# TSE_mother_board_CPU_commutation.net
KiCad netlist of a schematic drawn in Altium Designer
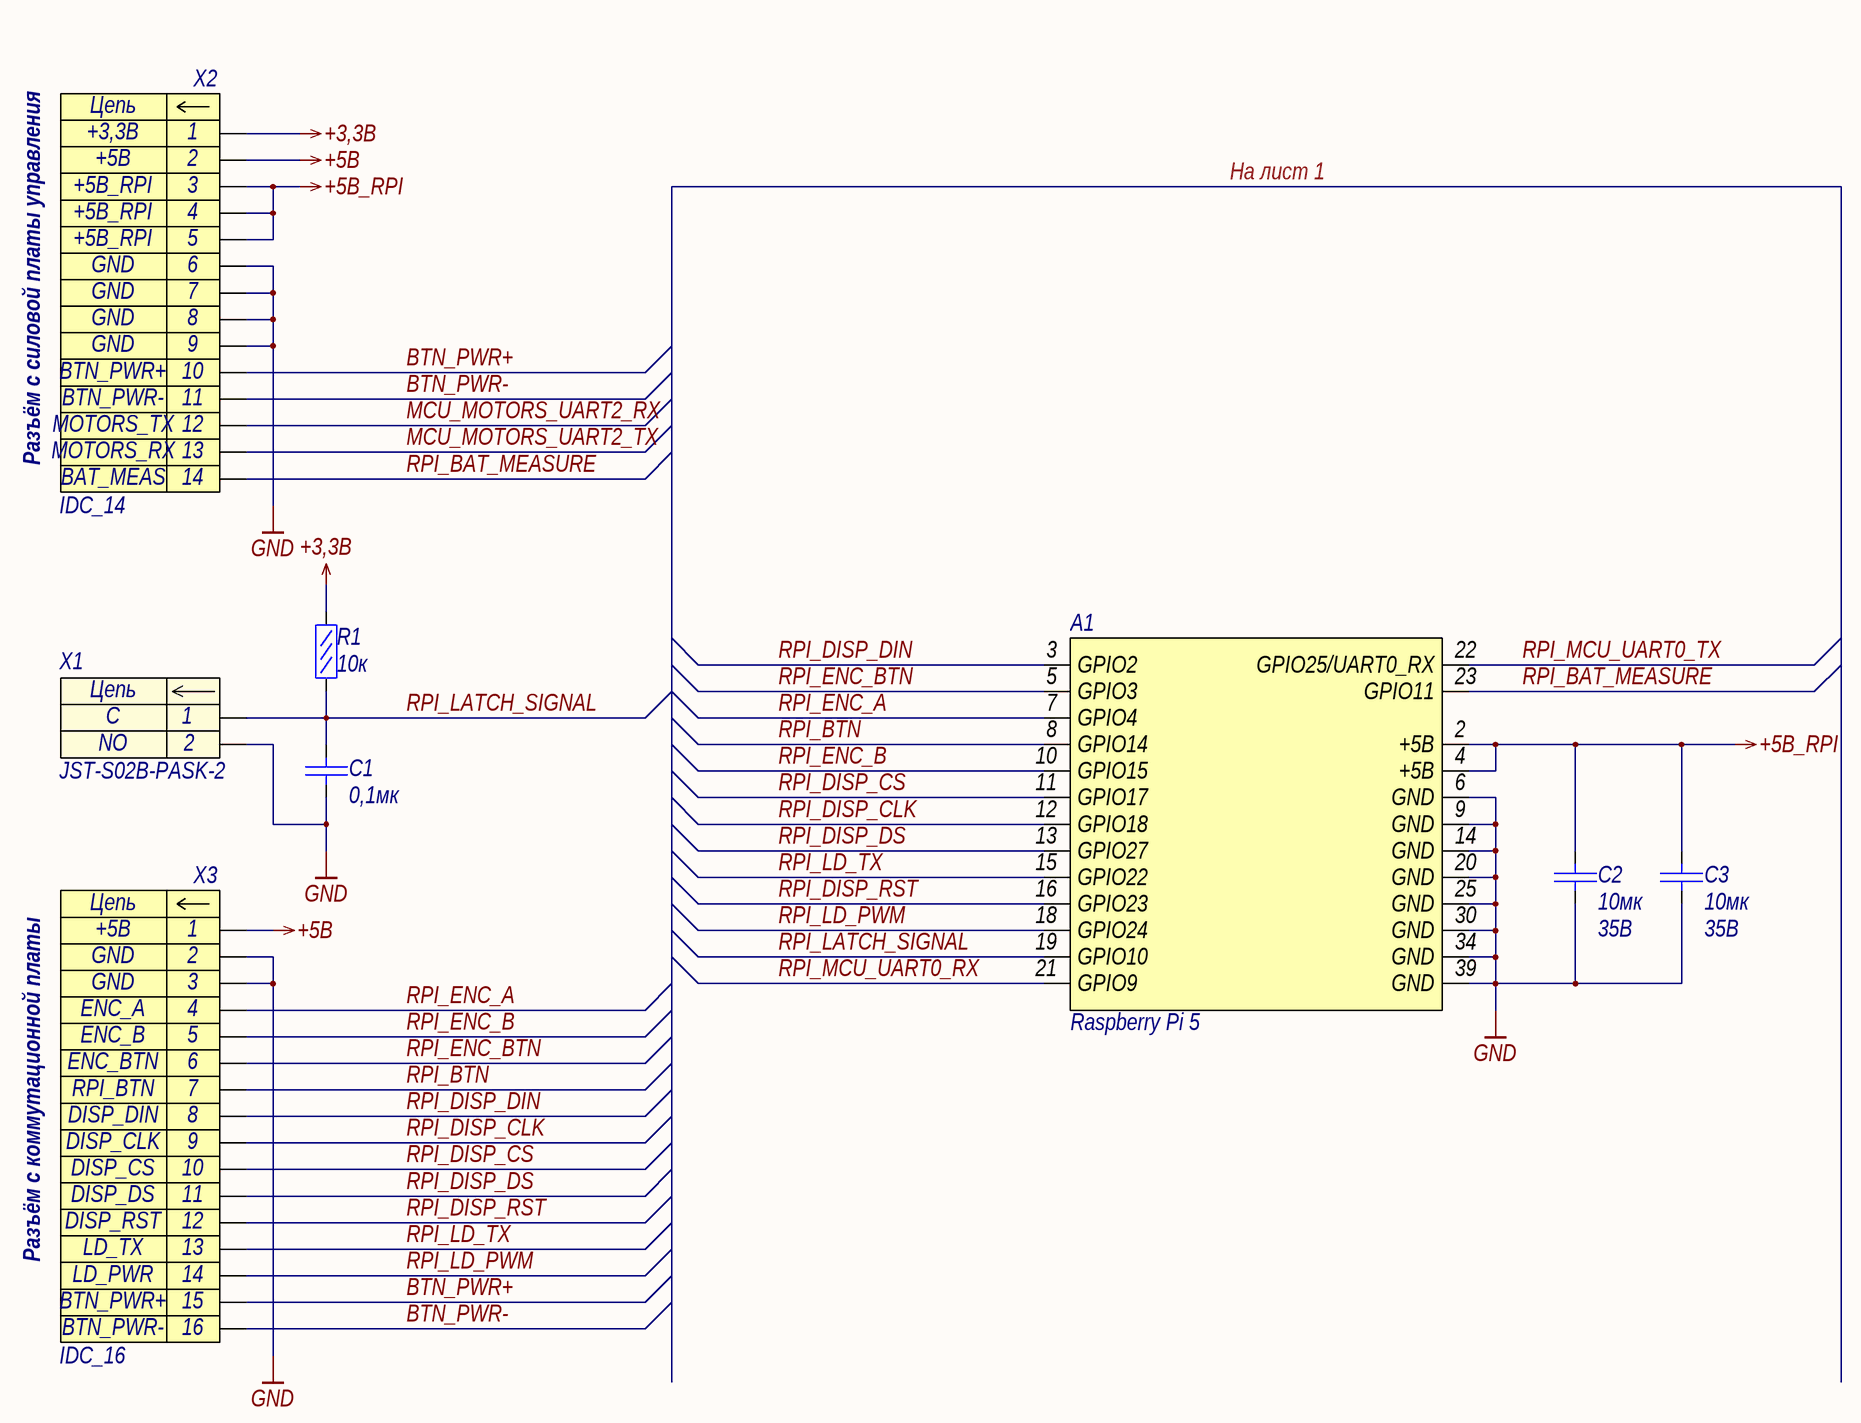
[diagram p0: TSE_mother_board_CPU_commutation.SchDoc]

(export (version "E")
  (design (tool "Eeschema 10.0.6"))
  (components
    (comp (ref "A1")
      (value "Raspberry Pi 5")
      (footprint "PLS_40")
      (description "Микрокомпьютер")
      (libsource (lib "ics") (part "Raspberry Pi 5"))
    )
    (comp (ref "C1")
      (value "0,1мк")
      (footprint "C0603")
      (description "Конденсатор кер. 0,1мкФ 50В")
      (fields (field (name "MANUFACTURER") "Yageo"))
      (libsource (lib "capacitors") (part "CC0603JPX7R9BB104"))
    )
    (comp (ref "C2")
      (value "10мк")
      (footprint "C1210")
      (description "Конденсатор кер. 10мкФ 35В")
      (fields (field (name "MANUFACTURER") "Yageo") (field (name "VOLTAGE") "35В"))
      (libsource (lib "capacitors") (part "CL32A106KATLNNE"))
    )
    (comp (ref "C3")
      (value "10мк")
      (footprint "C1210")
      (description "Конденсатор кер. 10мкФ 35В")
      (fields (field (name "MANUFACTURER") "Yageo") (field (name "VOLTAGE") "35В"))
      (libsource (lib "capacitors") (part "CL32A106KATLNNE"))
    )
    (comp (ref "R1")
      (value "10к")
      (footprint "R0603")
      (description "Резистор 10кОм 0,063Вт 1%")
      (fields (field (name "MANUFACTURER") "YAGEO") (field (name "TOLERANCE") "1%"))
      (libsource (lib "resistors") (part "RC0603FR-0710KL"))
    )
    (comp (ref "X1")
      (value "JST-S02B-PASK-2")
      (footprint "JST-S02B-PASK-2")
      (description "Разъем - 2 конт. угловая вилка на плату, шаг 2,00 мм")
      (libsource (lib "headers") (part "JST-S02B-PASK-2"))
    )
    (comp (ref "X2")
      (value "IDC_14")
      (footprint "IDC1.27_14")
      (description "Разъем - 14 конт. прямая вилка на плату")
      (libsource (lib "headers") (part "IDC_14"))
    )
    (comp (ref "X3")
      (value "IDC_16")
      (footprint "IDC1.27_16")
      (description "Разъем - 16 конт. прямая вилка на плату")
      (libsource (lib "headers") (part "IDC_16"))
    )
  )
  (nets
    (net (code "1") (name "+3,3В") (class "Default")
      (node (ref "R1") (pin "2") (pinfunction "2_2") (pintype "passive"))
      (node (ref "X2") (pin "1") (pinfunction "1_1") (pintype "passive"))
    )
    (net (code "2") (name "+5В") (class "Default")
      (node (ref "X2") (pin "2") (pinfunction "2_2") (pintype "passive"))
      (node (ref "X3") (pin "1") (pinfunction "1_1") (pintype "passive"))
    )
    (net (code "3") (name "+5В_RPI") (class "Default")
      (node (ref "A1") (pin "2") (pinfunction "+5В_2") (pintype "passive"))
      (node (ref "A1") (pin "4") (pinfunction "+5В_4") (pintype "passive"))
      (node (ref "C2") (pin "2") (pinfunction "2_2") (pintype "passive"))
      (node (ref "C3") (pin "2") (pinfunction "2_2") (pintype "passive"))
      (node (ref "X2") (pin "3") (pinfunction "3_3") (pintype "passive"))
      (node (ref "X2") (pin "4") (pinfunction "4_4") (pintype "passive"))
      (node (ref "X2") (pin "5") (pinfunction "5_5") (pintype "passive"))
    )
    (net (code "4") (name "/BTN_PWR+") (class "Default")
      (node (ref "X2") (pin "10") (pinfunction "10_10") (pintype "passive"))
      (node (ref "X3") (pin "15") (pinfunction "15_15") (pintype "passive"))
    )
    (net (code "5") (name "/BTN_PWR-") (class "Default")
      (node (ref "X2") (pin "11") (pinfunction "11_11") (pintype "passive"))
      (node (ref "X3") (pin "16") (pinfunction "16_16") (pintype "passive"))
    )
    (net (code "6") (name "/MCU_MOTORS_UART2_RX") (class "Default")
      (node (ref "X2") (pin "12") (pinfunction "12_12") (pintype "passive"))
    )
    (net (code "7") (name "/MCU_MOTORS_UART2_TX") (class "Default")
      (node (ref "X2") (pin "13") (pinfunction "13_13") (pintype "passive"))
    )
    (net (code "8") (name "/RPI_BAT_MEASURE") (class "Default")
      (node (ref "A1") (pin "23") (pinfunction "GPIO11_23") (pintype "passive"))
      (node (ref "X2") (pin "14") (pinfunction "14_14") (pintype "passive"))
    )
    (net (code "9") (name "/RPI_BTN") (class "Default")
      (node (ref "A1") (pin "8") (pinfunction "GPIO14_8") (pintype "passive"))
      (node (ref "X3") (pin "7") (pinfunction "7_7") (pintype "passive"))
    )
    (net (code "10") (name "/RPI_DISP_CLK") (class "Default")
      (node (ref "A1") (pin "12") (pinfunction "GPIO18_12") (pintype "passive"))
      (node (ref "X3") (pin "9") (pinfunction "9_9") (pintype "passive"))
    )
    (net (code "11") (name "/RPI_DISP_CS") (class "Default")
      (node (ref "A1") (pin "11") (pinfunction "GPIO17_11") (pintype "passive"))
      (node (ref "X3") (pin "10") (pinfunction "10_10") (pintype "passive"))
    )
    (net (code "12") (name "/RPI_DISP_DIN") (class "Default")
      (node (ref "A1") (pin "3") (pinfunction "GPIO2_3") (pintype "passive"))
      (node (ref "X3") (pin "8") (pinfunction "8_8") (pintype "passive"))
    )
    (net (code "13") (name "/RPI_DISP_DS") (class "Default")
      (node (ref "A1") (pin "13") (pinfunction "GPIO27_13") (pintype "passive"))
      (node (ref "X3") (pin "11") (pinfunction "11_11") (pintype "passive"))
    )
    (net (code "14") (name "/RPI_DISP_RST") (class "Default")
      (node (ref "A1") (pin "16") (pinfunction "GPIO23_16") (pintype "passive"))
      (node (ref "X3") (pin "12") (pinfunction "12_12") (pintype "passive"))
    )
    (net (code "15") (name "/RPI_ENC_A") (class "Default")
      (node (ref "A1") (pin "7") (pinfunction "GPIO4_7") (pintype "passive"))
      (node (ref "X3") (pin "4") (pinfunction "4_4") (pintype "passive"))
    )
    (net (code "16") (name "/RPI_ENC_B") (class "Default")
      (node (ref "A1") (pin "10") (pinfunction "GPIO15_10") (pintype "passive"))
      (node (ref "X3") (pin "5") (pinfunction "5_5") (pintype "passive"))
    )
    (net (code "17") (name "/RPI_ENC_BTN") (class "Default")
      (node (ref "A1") (pin "5") (pinfunction "GPIO3_5") (pintype "passive"))
      (node (ref "X3") (pin "6") (pinfunction "6_6") (pintype "passive"))
    )
    (net (code "18") (name "/RPI_LATCH_SIGNAL") (class "Default")
      (node (ref "A1") (pin "19") (pinfunction "GPIO10_19") (pintype "passive"))
      (node (ref "C1") (pin "2") (pinfunction "2_2") (pintype "passive"))
      (node (ref "R1") (pin "1") (pinfunction "1_1") (pintype "passive"))
      (node (ref "X1") (pin "1") (pinfunction "1_1") (pintype "passive"))
    )
    (net (code "19") (name "/RPI_LD_PWM") (class "Default")
      (node (ref "A1") (pin "18") (pinfunction "GPIO24_18") (pintype "passive"))
      (node (ref "X3") (pin "14") (pinfunction "14_14") (pintype "passive"))
    )
    (net (code "20") (name "/RPI_LD_TX") (class "Default")
      (node (ref "A1") (pin "15") (pinfunction "GPIO22_15") (pintype "passive"))
      (node (ref "X3") (pin "13") (pinfunction "13_13") (pintype "passive"))
    )
    (net (code "21") (name "/RPI_MCU_UART0_RX") (class "Default")
      (node (ref "A1") (pin "21") (pinfunction "GPIO9_21") (pintype "passive"))
    )
    (net (code "22") (name "/RPI_MCU_UART0_TX") (class "Default")
      (node (ref "A1") (pin "22") (pinfunction "GPIO25/UART0_RX_22") (pintype "passive"))
    )
    (net (code "23") (name "GND") (class "Default")
      (node (ref "A1") (pin "14") (pinfunction "GND_14") (pintype "passive"))
      (node (ref "A1") (pin "20") (pinfunction "GND_20") (pintype "passive"))
      (node (ref "A1") (pin "25") (pinfunction "GND_25") (pintype "passive"))
      (node (ref "A1") (pin "30") (pinfunction "GND_30") (pintype "passive"))
      (node (ref "A1") (pin "34") (pinfunction "GND_34") (pintype "passive"))
      (node (ref "A1") (pin "39") (pinfunction "GND_39") (pintype "passive"))
      (node (ref "A1") (pin "6") (pinfunction "GND_6") (pintype "passive"))
      (node (ref "A1") (pin "9") (pinfunction "GND_9") (pintype "passive"))
      (node (ref "C1") (pin "1") (pinfunction "1_1") (pintype "passive"))
      (node (ref "C2") (pin "1") (pinfunction "1_1") (pintype "passive"))
      (node (ref "C3") (pin "1") (pinfunction "1_1") (pintype "passive"))
      (node (ref "X1") (pin "2") (pinfunction "2_2") (pintype "passive"))
      (node (ref "X2") (pin "6") (pinfunction "6_6") (pintype "passive"))
      (node (ref "X2") (pin "7") (pinfunction "7_7") (pintype "passive"))
      (node (ref "X2") (pin "8") (pinfunction "8_8") (pintype "passive"))
      (node (ref "X2") (pin "9") (pinfunction "9_9") (pintype "passive"))
      (node (ref "X3") (pin "2") (pinfunction "2_2") (pintype "passive"))
      (node (ref "X3") (pin "3") (pinfunction "3_3") (pintype "passive"))
    )
  )
)
